# SENSORS.net
KiCad netlist of a schematic drawn in Altium Designer
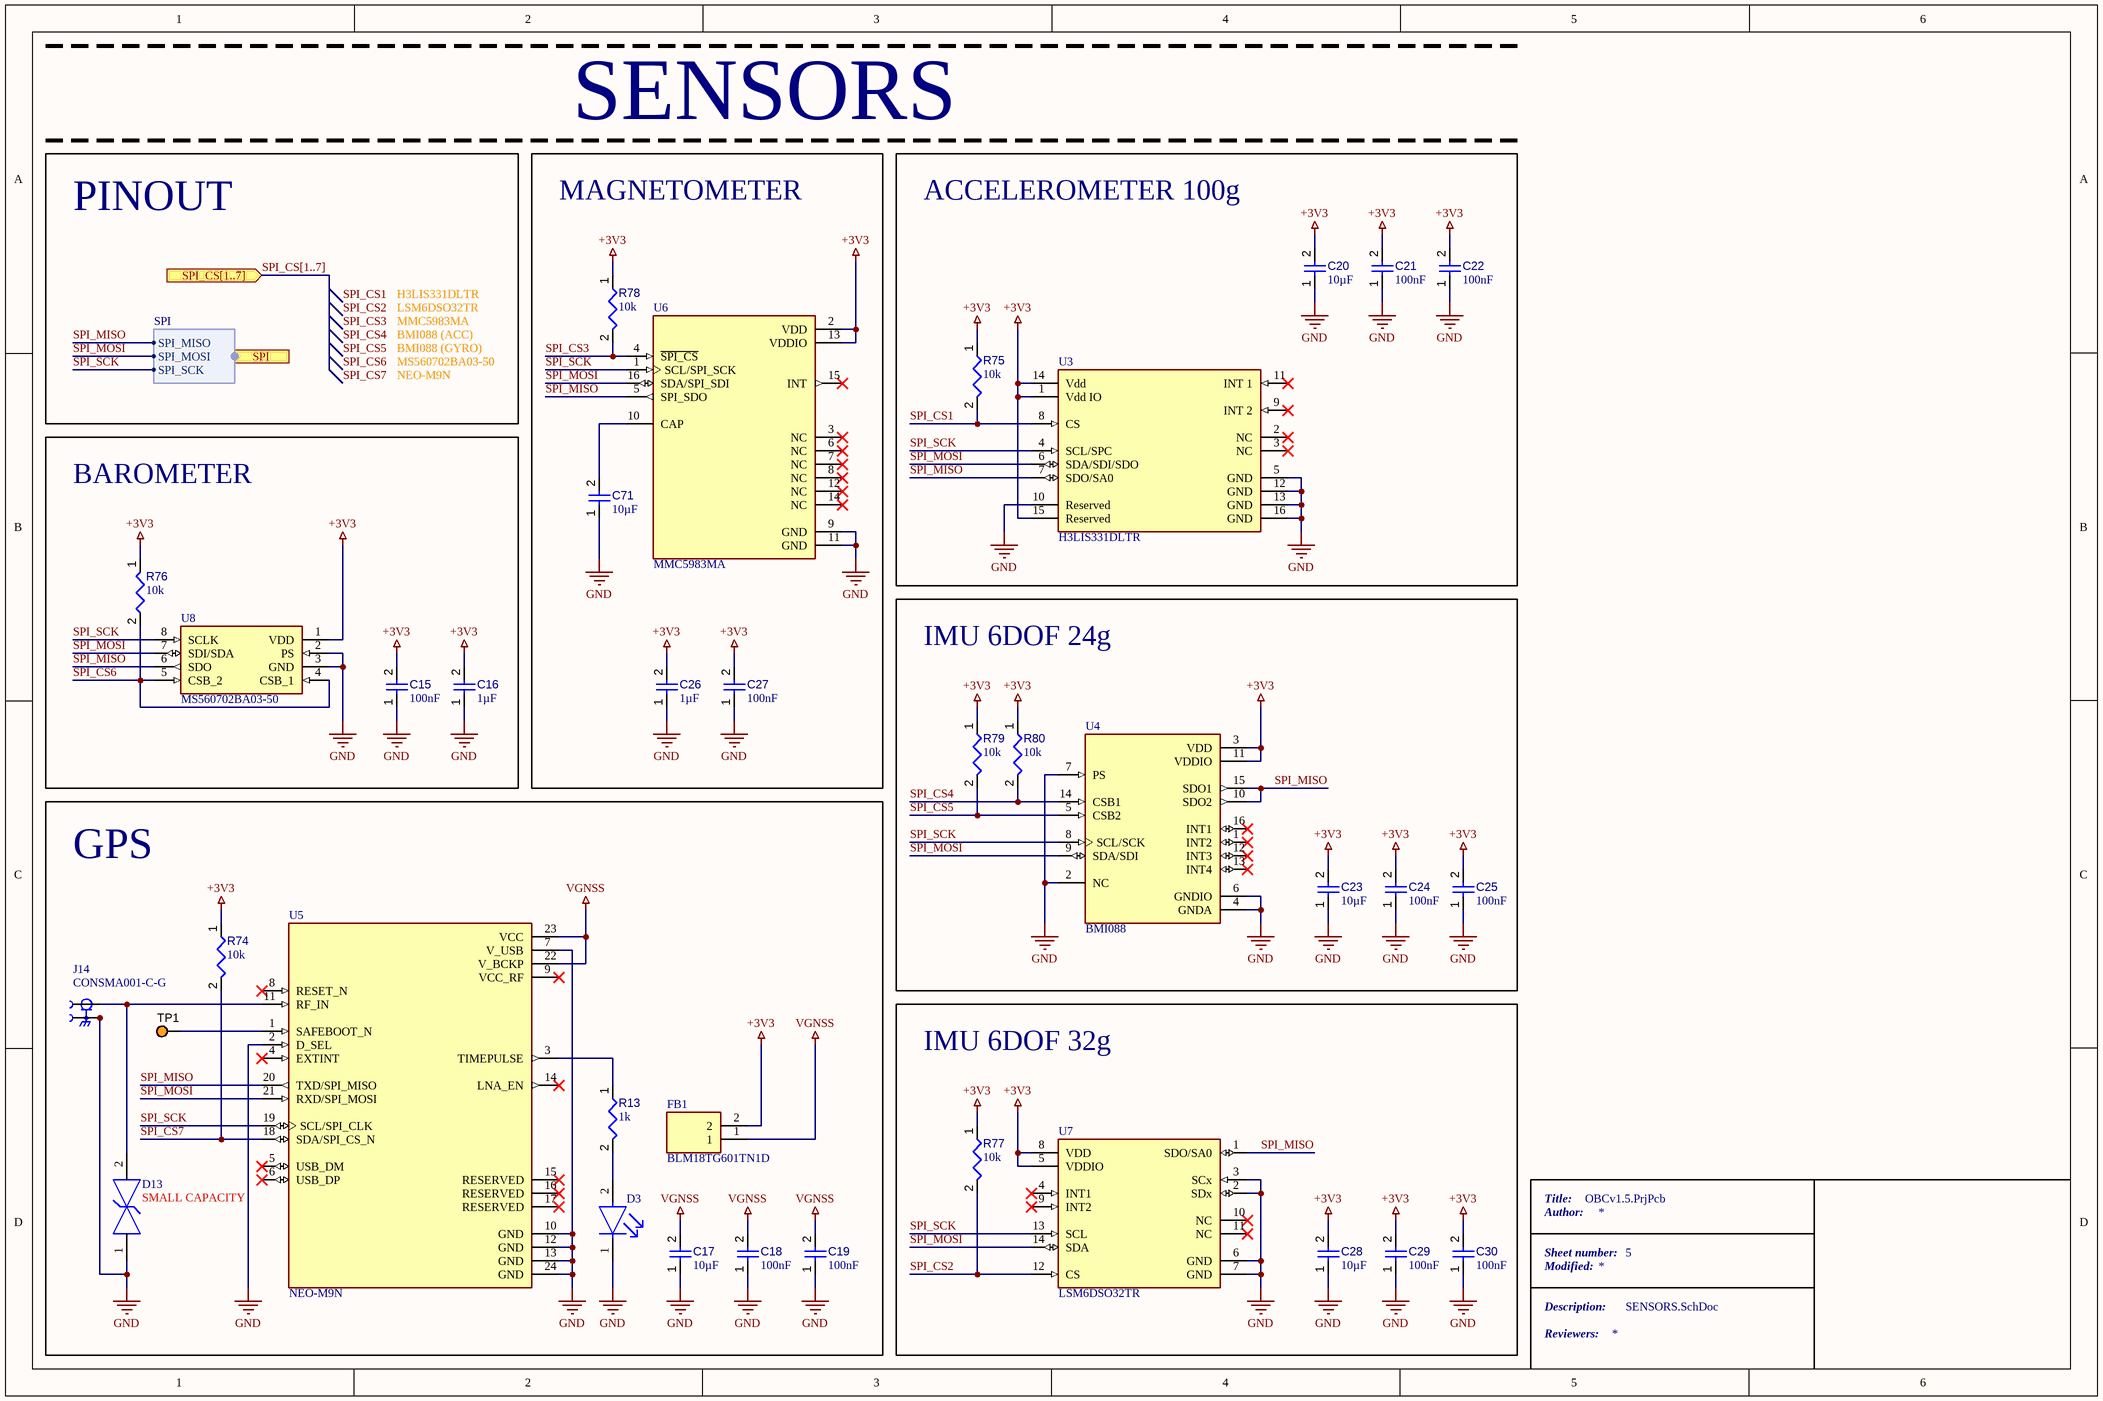
[diagram p0: SENSORS.SchDoc]

(export (version "E")
  (design (tool "Eeschema 10.0.6"))
  (components
    (comp (ref "C15")
      (value "100nF")
      (footprint "CAPC0402(1005)60_L")
      (description "Chip Capacitor, 100nF +/-20%, 10V, 0402, Thickness 0.6 mm")
      (fields (field (name "TOLERANCE") "20%") (field (name "Comment") "Capacitor 100nF +/-20% 10V 0402"))
      (libsource (lib "PWr in Space team") (part "CAP-NP-2"))
    )
    (comp (ref "C16")
      (value "1µF")
      (footprint "CAPC0402(1005)60_L")
      (description "Chip Capacitor, 1µF +/-20%, 10V, 0402, Thickness 0.6 mm")
      (fields (field (name "TOLERANCE") "10%") (field (name "Comment") "Capacitor 1µF +/-20% 10V 0402"))
      (libsource (lib "PWr in Space team") (part "CAP-NP-2"))
    )
    (comp (ref "C17")
      (value "10µF")
      (footprint "CAPC0603(1608)100_L")
      (description "Chip Capacitor, 10µF +/-20%, 10V, 0603, Thickness 1 mm")
      (fields (field (name "TOLERANCE") "10%") (field (name "Comment") "Capacitor 10µF +/-20% 10V 0603"))
      (libsource (lib "PWr in Space team") (part "CAP-NP-2"))
    )
    (comp (ref "C18")
      (value "100nF")
      (footprint "CAPC0402(1005)60_L")
      (description "Chip Capacitor, 100nF +/-20%, 10V, 0402, Thickness 0.6 mm")
      (fields (field (name "TOLERANCE") "20%") (field (name "Comment") "Capacitor 100nF +/-20% 10V 0402"))
      (libsource (lib "PWr in Space team") (part "CAP-NP-2"))
    )
    (comp (ref "C19")
      (value "100nF")
      (footprint "CAPC0402(1005)60_L")
      (description "Chip Capacitor, 100nF +/-20%, 10V, 0402, Thickness 0.6 mm")
      (fields (field (name "TOLERANCE") "20%") (field (name "Comment") "Capacitor 100nF +/-20% 10V 0402"))
      (libsource (lib "PWr in Space team") (part "CAP-NP-2"))
    )
    (comp (ref "C20")
      (value "10µF")
      (footprint "CAPC0603(1608)100_L")
      (description "Chip Capacitor, 10µF +/-20%, 10V, 0603, Thickness 1 mm")
      (fields (field (name "TOLERANCE") "10%") (field (name "Comment") "Capacitor 10µF +/-20% 10V 0603"))
      (libsource (lib "PWr in Space team") (part "CAP-NP-2"))
    )
    (comp (ref "C21")
      (value "100nF")
      (footprint "CAPC0402(1005)60_L")
      (description "Chip Capacitor, 100nF +/-20%, 10V, 0402, Thickness 0.6 mm")
      (fields (field (name "TOLERANCE") "20%") (field (name "Comment") "Capacitor 100nF +/-20% 10V 0402"))
      (libsource (lib "PWr in Space team") (part "CAP-NP-2"))
    )
    (comp (ref "C22")
      (value "100nF")
      (footprint "CAPC0402(1005)60_L")
      (description "Chip Capacitor, 100nF +/-20%, 10V, 0402, Thickness 0.6 mm")
      (fields (field (name "TOLERANCE") "20%") (field (name "Comment") "Capacitor 100nF +/-20% 10V 0402"))
      (libsource (lib "PWr in Space team") (part "CAP-NP-2"))
    )
    (comp (ref "C23")
      (value "10µF")
      (footprint "CAPC0603(1608)100_L")
      (description "Chip Capacitor, 10µF +/-20%, 10V, 0603, Thickness 1 mm")
      (fields (field (name "TOLERANCE") "10%") (field (name "Comment") "Capacitor 10µF +/-20% 10V 0603"))
      (libsource (lib "PWr in Space team") (part "CAP-NP-2"))
    )
    (comp (ref "C24")
      (value "100nF")
      (footprint "CAPC0402(1005)60_L")
      (description "Chip Capacitor, 100nF +/-20%, 10V, 0402, Thickness 0.6 mm")
      (fields (field (name "TOLERANCE") "20%") (field (name "Comment") "Capacitor 100nF +/-20% 10V 0402"))
      (libsource (lib "PWr in Space team") (part "CAP-NP-2"))
    )
    (comp (ref "C25")
      (value "100nF")
      (footprint "CAPC0402(1005)60_L")
      (description "Chip Capacitor, 100nF +/-20%, 10V, 0402, Thickness 0.6 mm")
      (fields (field (name "TOLERANCE") "20%") (field (name "Comment") "Capacitor 100nF +/-20% 10V 0402"))
      (libsource (lib "PWr in Space team") (part "CAP-NP-2"))
    )
    (comp (ref "C26")
      (value "1µF")
      (footprint "CAPC0402(1005)60_L")
      (description "Chip Capacitor, 1µF +/-20%, 10V, 0402, Thickness 0.6 mm")
      (fields (field (name "TOLERANCE") "10%") (field (name "Comment") "Capacitor 1µF +/-20% 10V 0402"))
      (libsource (lib "PWr in Space team") (part "CAP-NP-2"))
    )
    (comp (ref "C27")
      (value "100nF")
      (footprint "CAPC0402(1005)60_L")
      (description "Chip Capacitor, 100nF +/-20%, 10V, 0402, Thickness 0.6 mm")
      (fields (field (name "TOLERANCE") "20%") (field (name "Comment") "Capacitor 100nF +/-20% 10V 0402"))
      (libsource (lib "PWr in Space team") (part "CAP-NP-2"))
    )
    (comp (ref "C28")
      (value "10µF")
      (footprint "CAPC0603(1608)100_L")
      (description "Chip Capacitor, 10µF +/-20%, 10V, 0603, Thickness 1 mm")
      (fields (field (name "TOLERANCE") "10%") (field (name "Comment") "Capacitor 10µF +/-20% 10V 0603"))
      (libsource (lib "PWr in Space team") (part "CAP-NP-2"))
    )
    (comp (ref "C29")
      (value "100nF")
      (footprint "CAPC0402(1005)60_L")
      (description "Chip Capacitor, 100nF +/-20%, 10V, 0402, Thickness 0.6 mm")
      (fields (field (name "TOLERANCE") "20%") (field (name "Comment") "Capacitor 100nF +/-20% 10V 0402"))
      (libsource (lib "PWr in Space team") (part "CAP-NP-2"))
    )
    (comp (ref "C30")
      (value "100nF")
      (footprint "CAPC0402(1005)60_L")
      (description "Chip Capacitor, 100nF +/-20%, 10V, 0402, Thickness 0.6 mm")
      (fields (field (name "TOLERANCE") "20%") (field (name "Comment") "Capacitor 100nF +/-20% 10V 0402"))
      (libsource (lib "PWr in Space team") (part "CAP-NP-2"))
    )
    (comp (ref "C71")
      (value "10µF")
      (footprint "CAPC0603(1608)100_L")
      (description "Chip Capacitor, 10µF +/-20%, 10V, 0603, Thickness 1 mm")
      (fields (field (name "TOLERANCE") "10%") (field (name "Comment") "Capacitor 10µF +/-20% 10V 0603"))
      (libsource (lib "PWr in Space team") (part "CAP-NP-2"))
    )
    (comp (ref "D3")
      (value "D5")
      (footprint "FP-LTST-C191TBKT-MFG")
      (description "LED BLUE CLEAR CHIP SMD")
      (libsource (lib "Altium Content Vault") (part "8706943c75ba83719d021d2fdc84c58"))
    )
    (comp (ref "D13")
      (value "SMALL CAPACITY")
      (footprint "FP-PGB1-0402-MFG")
      (description "TVS DIODE 12V 250V 0402")
      (fields
        (field (name "OCTOPART") "https://octopart.com/pgb1010402kr-littelfuse-10444990")
        (field (name "MANUFACTURER PART NUMBER") "PGB1010402KR")
      )
      (libsource (lib "Altium Content Vault") (part "876f4347bf90aa6f500f43e3cd03972"))
    )
    (comp (ref "FB1")
      (value "BLM18TG601TN1D")
      (footprint "SamacSys:BLM18EG101TH1D")
      (description "Ferrite Bead")
      (fields (field (name "MOUSER PART NUMBER") "81-BLM18TG601TN1D"))
      (libsource (lib "*") (part "BLM18TG601TN1D"))
    )
    (comp (ref "J14")
      (value "CONSMA001-C-G")
      (footprint "LINX_CONSMA001-C-G")
      (fields (field (name "MF") "{'manufacturer': u'Linx Technologies'}"))
      (libsource (lib "SnapEDA_Library") (part "CONSMA001-C-G"))
    )
    (comp (ref "R13")
      (value "1k")
      (footprint "RESC0402(1005)_L")
      (description "Chip Resistor, 1 kOhms, +/-5 %, 63 mW, -55 to 155 degC, 0402")
      (fields (field (name "TOLERANCE") "5%") (field (name "POWER") "63mW"))
      (libsource (lib "PWr in Space team") (part "RES-2"))
    )
    (comp (ref "R74")
      (value "10k")
      (footprint "RESC0402(1005)_L")
      (description "Chip Resistor, 10 kOhms, +/-1 %, 63 mW, -55 to 125 degC, 0402")
      (fields (field (name "POWER") "63mW") (field (name "TOLERANCE") "1%"))
      (libsource (lib "PWr in Space team") (part "RES-2"))
    )
    (comp (ref "R75")
      (value "10k")
      (footprint "RESC0402(1005)_L")
      (description "Chip Resistor, 10 kOhms, +/-1 %, 63 mW, -55 to 125 degC, 0402")
      (fields (field (name "POWER") "63mW") (field (name "TOLERANCE") "1%"))
      (libsource (lib "PWr in Space team") (part "RES-2"))
    )
    (comp (ref "R76")
      (value "10k")
      (footprint "RESC0402(1005)_L")
      (description "Chip Resistor, 10 kOhms, +/-1 %, 63 mW, -55 to 125 degC, 0402")
      (fields (field (name "POWER") "63mW") (field (name "TOLERANCE") "1%"))
      (libsource (lib "PWr in Space team") (part "RES-2"))
    )
    (comp (ref "R77")
      (value "10k")
      (footprint "RESC0402(1005)_L")
      (description "Chip Resistor, 10 kOhms, +/-1 %, 63 mW, -55 to 125 degC, 0402")
      (fields (field (name "POWER") "63mW") (field (name "TOLERANCE") "1%"))
      (libsource (lib "PWr in Space team") (part "RES-2"))
    )
    (comp (ref "R78")
      (value "10k")
      (footprint "RESC0402(1005)_L")
      (description "Chip Resistor, 10 kOhms, +/-1 %, 63 mW, -55 to 125 degC, 0402")
      (fields (field (name "POWER") "63mW") (field (name "TOLERANCE") "1%"))
      (libsource (lib "PWr in Space team") (part "RES-2"))
    )
    (comp (ref "R79")
      (value "10k")
      (footprint "RESC0402(1005)_L")
      (description "Chip Resistor, 10 kOhms, +/-1 %, 63 mW, -55 to 125 degC, 0402")
      (fields (field (name "POWER") "63mW") (field (name "TOLERANCE") "1%"))
      (libsource (lib "PWr in Space team") (part "RES-2"))
    )
    (comp (ref "R80")
      (value "10k")
      (footprint "RESC0402(1005)_L")
      (description "Chip Resistor, 10 kOhms, +/-1 %, 63 mW, -55 to 125 degC, 0402")
      (fields (field (name "POWER") "63mW") (field (name "TOLERANCE") "1%"))
      (libsource (lib "PWr in Space team") (part "RES-2"))
    )
    (comp (ref "TP1")
      (value "5003")
      (footprint "KSTN-5003")
      (description "Test Point, Orange, Height 4.6 mm, Tail Length 3 mm, 1-Pin THD, RoHS")
      (fields (field (name "MANUFACTURER") "Keystone"))
      (libsource (lib "PWr in Space team") (part "TESTPOINT_ORANGE"))
    )
    (comp (ref "U3")
      (value "H3LIS331DLTR")
      (footprint "FP-TFLGA16-7983231-MFG")
      (description "ACCEL 100-400G I2C/SPI 16TFLGA")
      (fields
        (field (name "OCTOPART") "https://octopart.com/h3lis331dltr-stmicroelectronics-29186499")
        (field (name "MANUFACTURER") "STMicroelectronics")
      )
      (libsource (lib "Altium Content Vault") (part "88bf36ed36dec8c6247366cd2bff627"))
    )
    (comp (ref "U4")
      (value "BMI088")
      (footprint "PQFN50P450X300X100-16N")
      (fields (field (name "MF") "{'manufacturer': u'Bosch Sensortec'}"))
      (libsource (lib "SnapEDA_Library") (part "BMI088"))
    )
    (comp (ref "U5")
      (value "NEO-M9N")
      (footprint "XCVR_NEO-M9N")
      (fields (field (name "MF") "{'manufacturer': u'U-Blox'}"))
      (libsource (lib "SnapEDA_Library") (part "NEO-M9N"))
    )
    (comp (ref "U6")
      (value "MMC5983MA")
      (footprint "PQFN50P300X300X100-16N")
      (description "MMC5983 series Magnetic, Magnetometer Sensor Evaluation Board")
      (fields (field (name "MF") "{'manufacturer': u'Memsic Inc.'}"))
      (libsource (lib "SnapEDA_Library") (part "MMC5983MA"))
    )
    (comp (ref "U7")
      (value "LSM6DSO32TR")
      (footprint "FP-LGA-14L-DM00249496-MFG")
      (description "INEMO INERTIAL MODULE: 3D ACCELE")
      (libsource (lib "Altium Content Vault") (part "593856c316c551aebc7657d93cdb4f0"))
    )
    (comp (ref "U8")
      (value "MS560702BA03-50")
      (footprint "SamacSys:MS5607-02BA03")
      (description "Integrated Circuit")
      (fields (field (name "MOUSER PART NUMBER") "824-MS560702BA03-50"))
      (libsource (lib "*") (part "MS560702BA03-50"))
    )
  )
  (nets
    (net (code "2") (name "+3V3") (class "Default")
      (node (ref "C15") (pin "2") (pinfunction "2_2") (pintype "passive"))
      (node (ref "C16") (pin "2") (pinfunction "2_2") (pintype "passive"))
      (node (ref "C20") (pin "2") (pinfunction "2_2") (pintype "passive"))
      (node (ref "C21") (pin "2") (pinfunction "2_2") (pintype "passive"))
      (node (ref "C22") (pin "2") (pinfunction "2_2") (pintype "passive"))
      (node (ref "C23") (pin "2") (pinfunction "2_2") (pintype "passive"))
      (node (ref "C24") (pin "2") (pinfunction "2_2") (pintype "passive"))
      (node (ref "C25") (pin "2") (pinfunction "2_2") (pintype "passive"))
      (node (ref "C26") (pin "2") (pinfunction "2_2") (pintype "passive"))
      (node (ref "C27") (pin "2") (pinfunction "2_2") (pintype "passive"))
      (node (ref "C28") (pin "2") (pinfunction "2_2") (pintype "passive"))
      (node (ref "C29") (pin "2") (pinfunction "2_2") (pintype "passive"))
      (node (ref "C30") (pin "2") (pinfunction "2_2") (pintype "passive"))
      (node (ref "FB1") (pin "2") (pinfunction "2_2") (pintype "passive"))
      (node (ref "R74") (pin "1") (pinfunction "1_1") (pintype "passive"))
      (node (ref "R75") (pin "1") (pinfunction "1_1") (pintype "passive"))
      (node (ref "R76") (pin "1") (pinfunction "1_1") (pintype "passive"))
      (node (ref "R77") (pin "1") (pinfunction "1_1") (pintype "passive"))
      (node (ref "R78") (pin "1") (pinfunction "1_1") (pintype "passive"))
      (node (ref "R79") (pin "1") (pinfunction "1_1") (pintype "passive"))
      (node (ref "R80") (pin "1") (pinfunction "1_1") (pintype "passive"))
      (node (ref "U3") (pin "1") (pinfunction "Vdd_IO_1") (pintype "power_in"))
      (node (ref "U3") (pin "14") (pinfunction "Vdd_14") (pintype "power_in"))
      (node (ref "U3") (pin "15") (pinfunction "Reserved_15") (pintype "passive"))
      (node (ref "U4") (pin "11") (pinfunction "VDDIO_11") (pintype "power_in"))
      (node (ref "U4") (pin "3") (pinfunction "VDD_3") (pintype "power_in"))
      (node (ref "U6") (pin "13") (pinfunction "VDDIO_13") (pintype "power_in"))
      (node (ref "U6") (pin "2") (pinfunction "VDD_2") (pintype "power_in"))
      (node (ref "U7") (pin "5") (pinfunction "VDDIO_5") (pintype "power_in"))
      (node (ref "U7") (pin "8") (pinfunction "VDD_8") (pintype "power_in"))
      (node (ref "U8") (pin "1") (pinfunction "VDD_1") (pintype "power_in"))
    )
    (net (code "3") (name "/SPI_CS1") (class "Default")
      (node (ref "R75") (pin "2") (pinfunction "2_2") (pintype "passive"))
      (node (ref "U3") (pin "8") (pinfunction "CS_8") (pintype "input"))
    )
    (net (code "4") (name "/SPI_CS2") (class "Default")
      (node (ref "R77") (pin "2") (pinfunction "2_2") (pintype "passive"))
      (node (ref "U7") (pin "12") (pinfunction "CS_12") (pintype "input"))
    )
    (net (code "5") (name "/SPI_CS3") (class "Default")
      (node (ref "R78") (pin "2") (pinfunction "2_2") (pintype "passive"))
      (node (ref "U6") (pin "4") (pinfunction "~{SPI_CS}_4") (pintype "input"))
    )
    (net (code "6") (name "/SPI_CS4") (class "Default")
      (node (ref "R80") (pin "2") (pinfunction "2_2") (pintype "passive"))
      (node (ref "U4") (pin "14") (pinfunction "CSB1_14") (pintype "input"))
    )
    (net (code "7") (name "/SPI_CS5") (class "Default")
      (node (ref "R79") (pin "2") (pinfunction "2_2") (pintype "passive"))
      (node (ref "U4") (pin "5") (pinfunction "CSB2_5") (pintype "input"))
    )
    (net (code "8") (name "/SPI_CS6") (class "Default")
      (node (ref "R76") (pin "2") (pinfunction "2_2") (pintype "passive"))
      (node (ref "U8") (pin "4") (pinfunction "CSB_1_4") (pintype "input"))
      (node (ref "U8") (pin "5") (pinfunction "CSB_2_5") (pintype "input"))
    )
    (net (code "9") (name "/SPI_CS7") (class "Default")
      (node (ref "R74") (pin "2") (pinfunction "2_2") (pintype "passive"))
      (node (ref "U5") (pin "18") (pinfunction "SDA/SPI_CS_N_18") (pintype "bidirectional"))
    )
    (net (code "11") (name "/SPI_MISO") (class "Default")
      (node (ref "U3") (pin "7") (pinfunction "SDO/SA0_7") (pintype "bidirectional"))
      (node (ref "U4") (pin "10") (pinfunction "SDO2_10") (pintype "output"))
      (node (ref "U4") (pin "15") (pinfunction "SDO1_15") (pintype "output"))
      (node (ref "U5") (pin "20") (pinfunction "TXD/SPI_MISO_20") (pintype "output"))
      (node (ref "U6") (pin "5") (pinfunction "SPI_SDO_5") (pintype "output"))
      (node (ref "U7") (pin "1") (pinfunction "SDO/SA0_1") (pintype "bidirectional"))
      (node (ref "U8") (pin "6") (pinfunction "SDO_6") (pintype "output"))
    )
    (net (code "12") (name "/SPI_MOSI") (class "Default")
      (node (ref "U3") (pin "6") (pinfunction "SDA/SDI/SDO_6") (pintype "bidirectional"))
      (node (ref "U4") (pin "9") (pinfunction "SDA/SDI_9") (pintype "bidirectional"))
      (node (ref "U5") (pin "21") (pinfunction "RXD/SPI_MOSI_21") (pintype "input"))
      (node (ref "U6") (pin "16") (pinfunction "SDA/SPI_SDI_16") (pintype "bidirectional"))
      (node (ref "U7") (pin "14") (pinfunction "SDA_14") (pintype "bidirectional"))
      (node (ref "U8") (pin "7") (pinfunction "SDI/SDA_7") (pintype "bidirectional"))
    )
    (net (code "13") (name "/SPI_SCK") (class "Default")
      (node (ref "U3") (pin "4") (pinfunction "SCL/SPC_4") (pintype "input"))
      (node (ref "U4") (pin "8") (pinfunction "SCL/SCK_8") (pintype "input"))
      (node (ref "U5") (pin "19") (pinfunction "SCL/SPI_CLK_19") (pintype "bidirectional"))
      (node (ref "U6") (pin "1") (pinfunction "SCL/SPI_SCK_1") (pintype "input"))
      (node (ref "U7") (pin "13") (pinfunction "SCL_13") (pintype "input"))
      (node (ref "U8") (pin "8") (pinfunction "SCLK_8") (pintype "input"))
    )
    (net (code "15") (name "GND") (class "Default")
      (node (ref "C15") (pin "1") (pinfunction "1_1") (pintype "passive"))
      (node (ref "C16") (pin "1") (pinfunction "1_1") (pintype "passive"))
      (node (ref "C17") (pin "1") (pinfunction "1_1") (pintype "passive"))
      (node (ref "C18") (pin "1") (pinfunction "1_1") (pintype "passive"))
      (node (ref "C19") (pin "1") (pinfunction "1_1") (pintype "passive"))
      (node (ref "C20") (pin "1") (pinfunction "1_1") (pintype "passive"))
      (node (ref "C21") (pin "1") (pinfunction "1_1") (pintype "passive"))
      (node (ref "C22") (pin "1") (pinfunction "1_1") (pintype "passive"))
      (node (ref "C23") (pin "1") (pinfunction "1_1") (pintype "passive"))
      (node (ref "C24") (pin "1") (pinfunction "1_1") (pintype "passive"))
      (node (ref "C25") (pin "1") (pinfunction "1_1") (pintype "passive"))
      (node (ref "C26") (pin "1") (pinfunction "1_1") (pintype "passive"))
      (node (ref "C27") (pin "1") (pinfunction "1_1") (pintype "passive"))
      (node (ref "C28") (pin "1") (pinfunction "1_1") (pintype "passive"))
      (node (ref "C29") (pin "1") (pinfunction "1_1") (pintype "passive"))
      (node (ref "C30") (pin "1") (pinfunction "1_1") (pintype "passive"))
      (node (ref "C71") (pin "1") (pinfunction "1_1") (pintype "passive"))
      (node (ref "D13") (pin "1") (pinfunction "1_1") (pintype "passive"))
      (node (ref "D3") (pin "1") (pinfunction "C_1") (pintype "passive"))
      (node (ref "J14") (pin "S1") (pinfunction "2_S1") (pintype "passive"))
      (node (ref "J14") (pin "S2") (pinfunction "2_S2") (pintype "passive"))
      (node (ref "J14") (pin "S3") (pinfunction "2_S3") (pintype "passive"))
      (node (ref "J14") (pin "S4") (pinfunction "2_S4") (pintype "passive"))
      (node (ref "U3") (pin "10") (pinfunction "Reserved_10") (pintype "passive"))
      (node (ref "U3") (pin "12") (pinfunction "GND_12") (pintype "power_in"))
      (node (ref "U3") (pin "13") (pinfunction "GND_13") (pintype "power_in"))
      (node (ref "U3") (pin "16") (pinfunction "GND_16") (pintype "power_in"))
      (node (ref "U3") (pin "5") (pinfunction "GND_5") (pintype "power_in"))
      (node (ref "U4") (pin "2") (pinfunction "NC_2") (pintype "passive"))
      (node (ref "U4") (pin "4") (pinfunction "GNDA_4") (pintype "power_in"))
      (node (ref "U4") (pin "6") (pinfunction "GNDIO_6") (pintype "power_in"))
      (node (ref "U4") (pin "7") (pinfunction "PS_7") (pintype "input"))
      (node (ref "U5") (pin "10") (pinfunction "GND_10") (pintype "power_in"))
      (node (ref "U5") (pin "12") (pinfunction "GND_12") (pintype "power_in"))
      (node (ref "U5") (pin "13") (pinfunction "GND_13") (pintype "power_in"))
      (node (ref "U5") (pin "2") (pinfunction "D_SEL_2") (pintype "input"))
      (node (ref "U5") (pin "24") (pinfunction "GND_24") (pintype "power_in"))
      (node (ref "U5") (pin "7") (pinfunction "V_USB_7") (pintype "power_in"))
      (node (ref "U6") (pin "11") (pinfunction "GND_11") (pintype "power_in"))
      (node (ref "U6") (pin "9") (pinfunction "GND_9") (pintype "power_in"))
      (node (ref "U7") (pin "2") (pinfunction "SDx_2") (pintype "bidirectional"))
      (node (ref "U7") (pin "3") (pinfunction "SCx_3") (pintype "input"))
      (node (ref "U7") (pin "6") (pinfunction "GND_6") (pintype "power_in"))
      (node (ref "U7") (pin "7") (pinfunction "GND_7") (pintype "power_in"))
      (node (ref "U8") (pin "2") (pinfunction "PS_2") (pintype "input"))
      (node (ref "U8") (pin "3") (pinfunction "GND_3") (pintype "power_in"))
    )
    (net (code "16") (name "Net-(D3-A)") (class "Default")
      (node (ref "D3") (pin "2") (pinfunction "A_2") (pintype "passive"))
      (node (ref "R13") (pin "2") (pinfunction "2_2") (pintype "passive"))
    )
    (net (code "17") (name "Net-(U5-RF_IN)") (class "Default")
      (node (ref "D13") (pin "2") (pinfunction "2_2") (pintype "passive"))
      (node (ref "J14") (pin "1") (pinfunction "1_1") (pintype "passive"))
      (node (ref "U5") (pin "11") (pinfunction "RF_IN_11") (pintype "input"))
    )
    (net (code "18") (name "Net-(U5-SAFEBOOT_N)") (class "Default")
      (node (ref "TP1") (pin "1") (pinfunction "1_1") (pintype "passive"))
      (node (ref "U5") (pin "1") (pinfunction "SAFEBOOT_N_1") (pintype "input"))
    )
    (net (code "19") (name "Net-(U5-TIMEPULSE)") (class "Default")
      (node (ref "R13") (pin "1") (pinfunction "1_1") (pintype "passive"))
      (node (ref "U5") (pin "3") (pinfunction "TIMEPULSE_3") (pintype "output"))
    )
    (net (code "20") (name "Net-(U6-CAP)") (class "Default")
      (node (ref "C71") (pin "2") (pinfunction "2_2") (pintype "passive"))
      (node (ref "U6") (pin "10") (pinfunction "CAP_10") (pintype "passive"))
    )
    (net (code "21") (name "VGNSS") (class "Default")
      (node (ref "C17") (pin "2") (pinfunction "2_2") (pintype "passive"))
      (node (ref "C18") (pin "2") (pinfunction "2_2") (pintype "passive"))
      (node (ref "C19") (pin "2") (pinfunction "2_2") (pintype "passive"))
      (node (ref "FB1") (pin "1") (pinfunction "1_1") (pintype "passive"))
      (node (ref "U5") (pin "22") (pinfunction "V_BCKP_22") (pintype "power_in"))
      (node (ref "U5") (pin "23") (pinfunction "VCC_23") (pintype "power_in"))
    )
    (net (code "22") (name "unconnected-(U3-INT_1-Pad11)") (class "Default")
      (node (ref "U3") (pin "11") (pinfunction "INT_1_11") (pintype "input+no_connect"))
    )
    (net (code "23") (name "unconnected-(U3-INT_2-Pad9)") (class "Default")
      (node (ref "U3") (pin "9") (pinfunction "INT_2_9") (pintype "input+no_connect"))
    )
    (net (code "24") (name "unconnected-(U3-NC-Pad2)") (class "Default")
      (node (ref "U3") (pin "2") (pinfunction "NC_2") (pintype "passive+no_connect"))
    )
    (net (code "25") (name "unconnected-(U3-NC-Pad3)") (class "Default")
      (node (ref "U3") (pin "3") (pinfunction "NC_3") (pintype "passive+no_connect"))
    )
    (net (code "26") (name "unconnected-(U4-INT1-Pad16)") (class "Default")
      (node (ref "U4") (pin "16") (pinfunction "INT1_16") (pintype "bidirectional+no_connect"))
    )
    (net (code "27") (name "unconnected-(U4-INT2-Pad1)") (class "Default")
      (node (ref "U4") (pin "1") (pinfunction "INT2_1") (pintype "bidirectional+no_connect"))
    )
    (net (code "28") (name "unconnected-(U4-INT3-Pad12)") (class "Default")
      (node (ref "U4") (pin "12") (pinfunction "INT3_12") (pintype "bidirectional+no_connect"))
    )
    (net (code "29") (name "unconnected-(U4-INT4-Pad13)") (class "Default")
      (node (ref "U4") (pin "13") (pinfunction "INT4_13") (pintype "bidirectional+no_connect"))
    )
    (net (code "30") (name "unconnected-(U5-EXTINT-Pad4)") (class "Default")
      (node (ref "U5") (pin "4") (pinfunction "EXTINT_4") (pintype "input+no_connect"))
    )
    (net (code "31") (name "unconnected-(U5-LNA_EN-Pad14)") (class "Default")
      (node (ref "U5") (pin "14") (pinfunction "LNA_EN_14") (pintype "output+no_connect"))
    )
    (net (code "32") (name "unconnected-(U5-RESERVED-Pad15)") (class "Default")
      (node (ref "U5") (pin "15") (pinfunction "RESERVED_15") (pintype "passive+no_connect"))
    )
    (net (code "33") (name "unconnected-(U5-RESERVED-Pad16)") (class "Default")
      (node (ref "U5") (pin "16") (pinfunction "RESERVED_16") (pintype "passive+no_connect"))
    )
    (net (code "34") (name "unconnected-(U5-RESERVED-Pad17)") (class "Default")
      (node (ref "U5") (pin "17") (pinfunction "RESERVED_17") (pintype "passive+no_connect"))
    )
    (net (code "35") (name "unconnected-(U5-RESET_N-Pad8)") (class "Default")
      (node (ref "U5") (pin "8") (pinfunction "RESET_N_8") (pintype "input+no_connect"))
    )
    (net (code "36") (name "unconnected-(U5-USB_DM-Pad5)") (class "Default")
      (node (ref "U5") (pin "5") (pinfunction "USB_DM_5") (pintype "bidirectional+no_connect"))
    )
    (net (code "37") (name "unconnected-(U5-USB_DP-Pad6)") (class "Default")
      (node (ref "U5") (pin "6") (pinfunction "USB_DP_6") (pintype "bidirectional+no_connect"))
    )
    (net (code "38") (name "unconnected-(U5-VCC_RF-Pad9)") (class "Default")
      (node (ref "U5") (pin "9") (pinfunction "VCC_RF_9") (pintype "power_in+no_connect"))
    )
    (net (code "39") (name "unconnected-(U6-INT-Pad15)") (class "Default")
      (node (ref "U6") (pin "15") (pinfunction "INT_15") (pintype "output+no_connect"))
    )
    (net (code "40") (name "unconnected-(U6-NC-Pad3)") (class "Default")
      (node (ref "U6") (pin "3") (pinfunction "NC_3") (pintype "passive+no_connect"))
    )
    (net (code "41") (name "unconnected-(U6-NC-Pad6)") (class "Default")
      (node (ref "U6") (pin "6") (pinfunction "NC_6") (pintype "passive+no_connect"))
    )
    (net (code "42") (name "unconnected-(U6-NC-Pad7)") (class "Default")
      (node (ref "U6") (pin "7") (pinfunction "NC_7") (pintype "passive+no_connect"))
    )
    (net (code "43") (name "unconnected-(U6-NC-Pad8)") (class "Default")
      (node (ref "U6") (pin "8") (pinfunction "NC_8") (pintype "passive+no_connect"))
    )
    (net (code "44") (name "unconnected-(U6-NC-Pad12)") (class "Default")
      (node (ref "U6") (pin "12") (pinfunction "NC_12") (pintype "passive+no_connect"))
    )
    (net (code "45") (name "unconnected-(U6-NC-Pad14)") (class "Default")
      (node (ref "U6") (pin "14") (pinfunction "NC_14") (pintype "passive+no_connect"))
    )
    (net (code "46") (name "unconnected-(U7-INT1-Pad4)") (class "Default")
      (node (ref "U7") (pin "4") (pinfunction "INT1_4") (pintype "input+no_connect"))
    )
    (net (code "47") (name "unconnected-(U7-INT2-Pad9)") (class "Default")
      (node (ref "U7") (pin "9") (pinfunction "INT2_9") (pintype "input+no_connect"))
    )
    (net (code "48") (name "unconnected-(U7-NC-Pad10)") (class "Default")
      (node (ref "U7") (pin "10") (pinfunction "NC_10") (pintype "passive+no_connect"))
    )
    (net (code "49") (name "unconnected-(U7-NC-Pad11)") (class "Default")
      (node (ref "U7") (pin "11") (pinfunction "NC_11") (pintype "passive+no_connect"))
    )
  )
)
